# Wildly_4Lipo_Charge.net
KiCad netlist of a schematic drawn in EAGLE
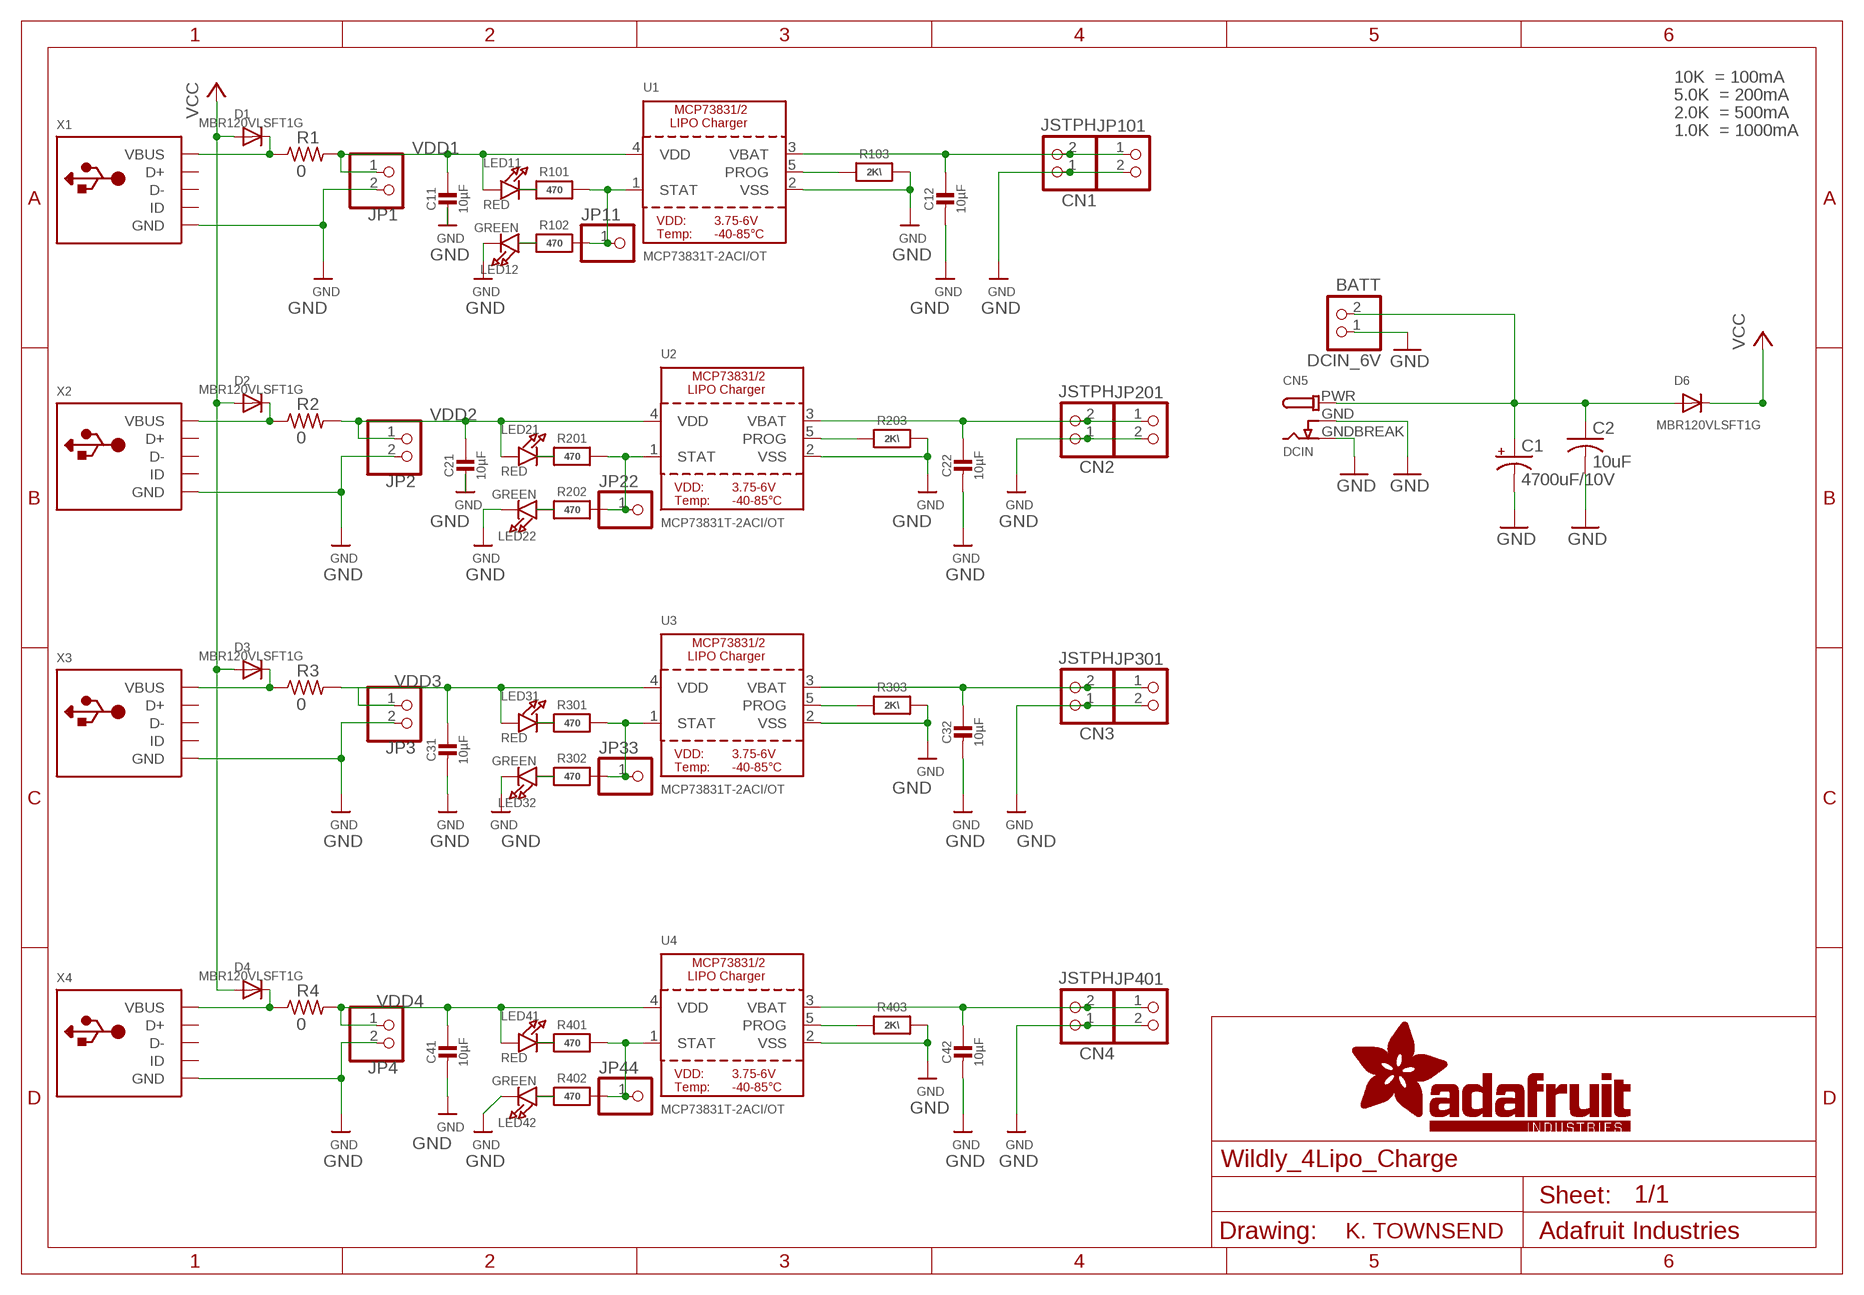
[diagram p0: schematic, sheet 1]

(export (version "E")
  (design (tool "Eeschema 10.0.6"))
  (components
    (comp (ref "C1")
      (value "4700uF/10V")
      (footprint "eagle-import:E5-13")
      (libsource (lib "eagle-import") (part "CPOL-USE5-13"))
    )
    (comp (ref "C2")
      (value "10uF")
      (footprint "eagle-import:C0805K")
      (libsource (lib "eagle-import") (part "C-USC0805K"))
    )
    (comp (ref "C11")
      (value "10µF")
      (footprint "eagle-import:0805-NO")
      (libsource (lib "eagle-import") (part "CAP_CERAMIC0805-NOOUTLINE"))
    )
    (comp (ref "C12")
      (value "10µF")
      (footprint "eagle-import:0805-NO")
      (libsource (lib "eagle-import") (part "CAP_CERAMIC0805-NOOUTLINE"))
    )
    (comp (ref "C21")
      (value "10µF")
      (footprint "eagle-import:0805-NO")
      (libsource (lib "eagle-import") (part "CAP_CERAMIC0805-NOOUTLINE"))
    )
    (comp (ref "C22")
      (value "10µF")
      (footprint "eagle-import:0805-NO")
      (libsource (lib "eagle-import") (part "CAP_CERAMIC0805-NOOUTLINE"))
    )
    (comp (ref "C31")
      (value "10µF")
      (footprint "eagle-import:0805-NO")
      (libsource (lib "eagle-import") (part "CAP_CERAMIC0805-NOOUTLINE"))
    )
    (comp (ref "C32")
      (value "10µF")
      (footprint "eagle-import:0805-NO")
      (libsource (lib "eagle-import") (part "CAP_CERAMIC0805-NOOUTLINE"))
    )
    (comp (ref "C41")
      (value "10µF")
      (footprint "eagle-import:0805-NO")
      (libsource (lib "eagle-import") (part "CAP_CERAMIC0805-NOOUTLINE"))
    )
    (comp (ref "C42")
      (value "10µF")
      (footprint "eagle-import:0805-NO")
      (libsource (lib "eagle-import") (part "CAP_CERAMIC0805-NOOUTLINE"))
    )
    (comp (ref "CN1")
      (value "JSTPH")
      (footprint "eagle-import:JSTPH2")
      (libsource (lib "eagle-import") (part "JST_2PIN"))
    )
    (comp (ref "CN2")
      (value "JSTPH")
      (footprint "eagle-import:JSTPH2")
      (libsource (lib "eagle-import") (part "JST_2PIN"))
    )
    (comp (ref "CN3")
      (value "JSTPH")
      (footprint "eagle-import:JSTPH2")
      (libsource (lib "eagle-import") (part "JST_2PIN"))
    )
    (comp (ref "CN4")
      (value "JSTPH")
      (footprint "eagle-import:JSTPH2")
      (libsource (lib "eagle-import") (part "JST_2PIN"))
    )
    (comp (ref "CN5")
      (value "DCIN")
      (footprint "eagle-import:DCJACK_2MM_SMT")
      (libsource (lib "eagle-import") (part "DCBARRELSMT"))
    )
    (comp (ref "D1")
      (value "MBR120VLSFT1G")
      (footprint "eagle-import:SOD-123")
      (libsource (lib "eagle-import") (part "DIODESOD-123"))
    )
    (comp (ref "D2")
      (value "MBR120VLSFT1G")
      (footprint "eagle-import:SOD-123")
      (libsource (lib "eagle-import") (part "DIODESOD-123"))
    )
    (comp (ref "D3")
      (value "MBR120VLSFT1G")
      (footprint "eagle-import:SOD-123")
      (libsource (lib "eagle-import") (part "DIODESOD-123"))
    )
    (comp (ref "D4")
      (value "MBR120VLSFT1G")
      (footprint "eagle-import:SOD-123")
      (libsource (lib "eagle-import") (part "DIODESOD-123"))
    )
    (comp (ref "D6")
      (value "MBR120VLSFT1G")
      (footprint "eagle-import:SOD-123")
      (libsource (lib "eagle-import") (part "DIODESOD-123"))
    )
    (comp (ref "DCIN_6V")
      (value "BATT")
      (footprint "eagle-import:1X02_ROUND")
      (libsource (lib "eagle-import") (part "HEADER-1X2ROUND"))
    )
    (comp (ref "JP1")
      (value "HEADER-1X2ROUND")
      (footprint "eagle-import:1X02_ROUND")
      (libsource (lib "eagle-import") (part "HEADER-1X2ROUND"))
    )
    (comp (ref "JP2")
      (value "HEADER-1X2ROUND")
      (footprint "eagle-import:1X02_ROUND")
      (libsource (lib "eagle-import") (part "HEADER-1X2ROUND"))
    )
    (comp (ref "JP3")
      (value "HEADER-1X2ROUND")
      (footprint "eagle-import:1X02_ROUND")
      (libsource (lib "eagle-import") (part "HEADER-1X2ROUND"))
    )
    (comp (ref "JP4")
      (value "HEADER-1X2ROUND")
      (footprint "eagle-import:1X02_ROUND")
      (libsource (lib "eagle-import") (part "HEADER-1X2ROUND"))
    )
    (comp (ref "JP11")
      (value "PINHD-1X1CB")
      (footprint "eagle-import:1X01-CLEANBIG")
      (libsource (lib "eagle-import") (part "PINHD-1X1CB"))
    )
    (comp (ref "JP22")
      (value "PINHD-1X1CB")
      (footprint "eagle-import:1X01-CLEANBIG")
      (libsource (lib "eagle-import") (part "PINHD-1X1CB"))
    )
    (comp (ref "JP33")
      (value "PINHD-1X1CB")
      (footprint "eagle-import:1X01-CLEANBIG")
      (libsource (lib "eagle-import") (part "PINHD-1X1CB"))
    )
    (comp (ref "JP44")
      (value "PINHD-1X1CB")
      (footprint "eagle-import:1X01-CLEANBIG")
      (libsource (lib "eagle-import") (part "PINHD-1X1CB"))
    )
    (comp (ref "JP101")
      (value "HEADER-1X2ROUND")
      (footprint "eagle-import:1X02_ROUND")
      (libsource (lib "eagle-import") (part "HEADER-1X2ROUND"))
    )
    (comp (ref "JP201")
      (value "HEADER-1X2ROUND")
      (footprint "eagle-import:1X02_ROUND")
      (libsource (lib "eagle-import") (part "HEADER-1X2ROUND"))
    )
    (comp (ref "JP301")
      (value "HEADER-1X2ROUND")
      (footprint "eagle-import:1X02_ROUND")
      (libsource (lib "eagle-import") (part "HEADER-1X2ROUND"))
    )
    (comp (ref "JP401")
      (value "HEADER-1X2ROUND")
      (footprint "eagle-import:1X02_ROUND")
      (libsource (lib "eagle-import") (part "HEADER-1X2ROUND"))
    )
    (comp (ref "LED11")
      (value "RED")
      (footprint "eagle-import:CHIPLED_0805_NOOUTLINE")
      (libsource (lib "eagle-import") (part "LED0805_NOOUTLINE"))
    )
    (comp (ref "LED12")
      (value "GREEN")
      (footprint "eagle-import:CHIPLED_0805_NOOUTLINE")
      (libsource (lib "eagle-import") (part "LED0805_NOOUTLINE"))
    )
    (comp (ref "LED21")
      (value "RED")
      (footprint "eagle-import:CHIPLED_0805_NOOUTLINE")
      (libsource (lib "eagle-import") (part "LED0805_NOOUTLINE"))
    )
    (comp (ref "LED22")
      (value "GREEN")
      (footprint "eagle-import:CHIPLED_0805_NOOUTLINE")
      (libsource (lib "eagle-import") (part "LED0805_NOOUTLINE"))
    )
    (comp (ref "LED31")
      (value "RED")
      (footprint "eagle-import:CHIPLED_0805_NOOUTLINE")
      (libsource (lib "eagle-import") (part "LED0805_NOOUTLINE"))
    )
    (comp (ref "LED32")
      (value "GREEN")
      (footprint "eagle-import:CHIPLED_0805_NOOUTLINE")
      (libsource (lib "eagle-import") (part "LED0805_NOOUTLINE"))
    )
    (comp (ref "LED41")
      (value "RED")
      (footprint "eagle-import:CHIPLED_0805_NOOUTLINE")
      (libsource (lib "eagle-import") (part "LED0805_NOOUTLINE"))
    )
    (comp (ref "LED42")
      (value "GREEN")
      (footprint "eagle-import:CHIPLED_0805_NOOUTLINE")
      (libsource (lib "eagle-import") (part "LED0805_NOOUTLINE"))
    )
    (comp (ref "R1")
      (value "0")
      (footprint "eagle-import:R0805")
      (libsource (lib "eagle-import") (part "R-US_R0805"))
    )
    (comp (ref "R2")
      (value "0")
      (footprint "eagle-import:R0805")
      (libsource (lib "eagle-import") (part "R-US_R0805"))
    )
    (comp (ref "R3")
      (value "0")
      (footprint "eagle-import:R0805")
      (libsource (lib "eagle-import") (part "R-US_R0805"))
    )
    (comp (ref "R4")
      (value "0")
      (footprint "eagle-import:R0805")
      (libsource (lib "eagle-import") (part "R-US_R0805"))
    )
    (comp (ref "R101")
      (value "470")
      (footprint "eagle-import:0805-NO")
      (libsource (lib "eagle-import") (part "RESISTOR0805_NOOUTLINE"))
    )
    (comp (ref "R102")
      (value "470")
      (footprint "eagle-import:0805-NO")
      (libsource (lib "eagle-import") (part "RESISTOR0805_NOOUTLINE"))
    )
    (comp (ref "R103")
      (value "2K\\")
      (footprint "eagle-import:0805-NO")
      (libsource (lib "eagle-import") (part "RESISTOR0805_NOOUTLINE"))
    )
    (comp (ref "R201")
      (value "470")
      (footprint "eagle-import:0805-NO")
      (libsource (lib "eagle-import") (part "RESISTOR0805_NOOUTLINE"))
    )
    (comp (ref "R202")
      (value "470")
      (footprint "eagle-import:0805-NO")
      (libsource (lib "eagle-import") (part "RESISTOR0805_NOOUTLINE"))
    )
    (comp (ref "R203")
      (value "2K\\")
      (footprint "eagle-import:0805-NO")
      (libsource (lib "eagle-import") (part "RESISTOR0805_NOOUTLINE"))
    )
    (comp (ref "R301")
      (value "470")
      (footprint "eagle-import:0805-NO")
      (libsource (lib "eagle-import") (part "RESISTOR0805_NOOUTLINE"))
    )
    (comp (ref "R302")
      (value "470")
      (footprint "eagle-import:0805-NO")
      (libsource (lib "eagle-import") (part "RESISTOR0805_NOOUTLINE"))
    )
    (comp (ref "R303")
      (value "2K\\")
      (footprint "eagle-import:0805-NO")
      (libsource (lib "eagle-import") (part "RESISTOR0805_NOOUTLINE"))
    )
    (comp (ref "R401")
      (value "470")
      (footprint "eagle-import:0805-NO")
      (libsource (lib "eagle-import") (part "RESISTOR0805_NOOUTLINE"))
    )
    (comp (ref "R402")
      (value "470")
      (footprint "eagle-import:0805-NO")
      (libsource (lib "eagle-import") (part "RESISTOR0805_NOOUTLINE"))
    )
    (comp (ref "R403")
      (value "2K\\")
      (footprint "eagle-import:0805-NO")
      (libsource (lib "eagle-import") (part "RESISTOR0805_NOOUTLINE"))
    )
    (comp (ref "U1")
      (value "MCP73831T-2ACI/OT")
      (footprint "eagle-import:SOT23-5")
      (libsource (lib "eagle-import") (part "MCP73831/2"))
    )
    (comp (ref "U2")
      (value "MCP73831T-2ACI/OT")
      (footprint "eagle-import:SOT23-5")
      (libsource (lib "eagle-import") (part "MCP73831/2"))
    )
    (comp (ref "U3")
      (value "MCP73831T-2ACI/OT")
      (footprint "eagle-import:SOT23-5")
      (libsource (lib "eagle-import") (part "MCP73831/2"))
    )
    (comp (ref "U4")
      (value "MCP73831T-2ACI/OT")
      (footprint "eagle-import:SOT23-5")
      (libsource (lib "eagle-import") (part "MCP73831/2"))
    )
    (comp (ref "X1")
      (value "USB_MEDIUM")
      (footprint "eagle-import:USB-MINI_MEDIUM")
      (libsource (lib "eagle-import") (part "USB_MEDIUM"))
    )
    (comp (ref "X2")
      (value "USB_MEDIUM")
      (footprint "eagle-import:USB-MINI_MEDIUM")
      (libsource (lib "eagle-import") (part "USB_MEDIUM"))
    )
    (comp (ref "X3")
      (value "USB_MEDIUM")
      (footprint "eagle-import:USB-MINI_MEDIUM")
      (libsource (lib "eagle-import") (part "USB_MEDIUM"))
    )
    (comp (ref "X4")
      (value "USB_MEDIUM")
      (footprint "eagle-import:USB-MINI_MEDIUM")
      (libsource (lib "eagle-import") (part "USB_MEDIUM"))
    )
  )
  (nets
    (net (code "1") (name "/VDD1") (class "Default")
      (node (ref "C11") (pin "1") (pinfunction "1_1") (pintype "passive"))
      (node (ref "JP1") (pin "1") (pinfunction "1_1") (pintype "passive"))
      (node (ref "LED11") (pin "A") (pinfunction "A_A") (pintype "passive"))
      (node (ref "R1") (pin "2") (pinfunction "2_2") (pintype "passive"))
      (node (ref "U1") (pin "4") (pinfunction "VDD_4") (pintype "power_in"))
    )
    (net (code "2") (name "/VDD2") (class "Default")
      (node (ref "C21") (pin "1") (pinfunction "1_1") (pintype "passive"))
      (node (ref "JP2") (pin "1") (pinfunction "1_1") (pintype "passive"))
      (node (ref "LED21") (pin "A") (pinfunction "A_A") (pintype "passive"))
      (node (ref "R2") (pin "2") (pinfunction "2_2") (pintype "passive"))
      (node (ref "U2") (pin "4") (pinfunction "VDD_4") (pintype "power_in"))
    )
    (net (code "3") (name "/VDD3") (class "Default")
      (node (ref "C31") (pin "1") (pinfunction "1_1") (pintype "passive"))
      (node (ref "JP3") (pin "1") (pinfunction "1_1") (pintype "passive"))
      (node (ref "LED31") (pin "A") (pinfunction "A_A") (pintype "passive"))
      (node (ref "R3") (pin "2") (pinfunction "2_2") (pintype "passive"))
      (node (ref "U3") (pin "4") (pinfunction "VDD_4") (pintype "power_in"))
    )
    (net (code "4") (name "/VDD4") (class "Default")
      (node (ref "C41") (pin "1") (pinfunction "1_1") (pintype "passive"))
      (node (ref "JP4") (pin "1") (pinfunction "1_1") (pintype "passive"))
      (node (ref "LED41") (pin "A") (pinfunction "A_A") (pintype "passive"))
      (node (ref "R4") (pin "2") (pinfunction "2_2") (pintype "passive"))
      (node (ref "U4") (pin "4") (pinfunction "VDD_4") (pintype "power_in"))
    )
    (net (code "5") (name "GND") (class "Default")
      (node (ref "C1") (pin "-") (pinfunction "-_-") (pintype "passive"))
      (node (ref "C11") (pin "2") (pinfunction "2_2") (pintype "passive"))
      (node (ref "C12") (pin "2") (pinfunction "2_2") (pintype "passive"))
      (node (ref "C2") (pin "2") (pinfunction "2_2") (pintype "passive"))
      (node (ref "C21") (pin "2") (pinfunction "2_2") (pintype "passive"))
      (node (ref "C22") (pin "2") (pinfunction "2_2") (pintype "passive"))
      (node (ref "C31") (pin "2") (pinfunction "2_2") (pintype "passive"))
      (node (ref "C32") (pin "2") (pinfunction "2_2") (pintype "passive"))
      (node (ref "C41") (pin "2") (pinfunction "2_2") (pintype "passive"))
      (node (ref "C42") (pin "2") (pinfunction "2_2") (pintype "passive"))
      (node (ref "CN1") (pin "1") (pinfunction "1_1") (pintype "passive"))
      (node (ref "CN2") (pin "1") (pinfunction "1_1") (pintype "passive"))
      (node (ref "CN3") (pin "1") (pinfunction "1_1") (pintype "passive"))
      (node (ref "CN4") (pin "1") (pinfunction "1_1") (pintype "passive"))
      (node (ref "CN5") (pin "GND") (pinfunction "GNDBREAK_GND") (pintype "power_in"))
      (node (ref "CN5") (pin "GNDBREAK") (pinfunction "GND_GNDBREAK") (pintype "power_in"))
      (node (ref "DCIN_6V") (pin "1") (pinfunction "1_1") (pintype "passive"))
      (node (ref "JP1") (pin "2") (pinfunction "2_2") (pintype "passive"))
      (node (ref "JP101") (pin "2") (pinfunction "2_2") (pintype "passive"))
      (node (ref "JP2") (pin "2") (pinfunction "2_2") (pintype "passive"))
      (node (ref "JP201") (pin "2") (pinfunction "2_2") (pintype "passive"))
      (node (ref "JP3") (pin "2") (pinfunction "2_2") (pintype "passive"))
      (node (ref "JP301") (pin "2") (pinfunction "2_2") (pintype "passive"))
      (node (ref "JP4") (pin "2") (pinfunction "2_2") (pintype "passive"))
      (node (ref "JP401") (pin "2") (pinfunction "2_2") (pintype "passive"))
      (node (ref "LED12") (pin "C") (pinfunction "C_C") (pintype "passive"))
      (node (ref "LED22") (pin "C") (pinfunction "C_C") (pintype "passive"))
      (node (ref "LED32") (pin "C") (pinfunction "C_C") (pintype "passive"))
      (node (ref "LED42") (pin "C") (pinfunction "C_C") (pintype "passive"))
      (node (ref "R103") (pin "2") (pinfunction "2_2") (pintype "passive"))
      (node (ref "R203") (pin "2") (pinfunction "2_2") (pintype "passive"))
      (node (ref "R303") (pin "2") (pinfunction "2_2") (pintype "passive"))
      (node (ref "R403") (pin "2") (pinfunction "2_2") (pintype "passive"))
      (node (ref "U1") (pin "2") (pinfunction "VSS_2") (pintype "power_in"))
      (node (ref "U2") (pin "2") (pinfunction "VSS_2") (pintype "power_in"))
      (node (ref "U3") (pin "2") (pinfunction "VSS_2") (pintype "power_in"))
      (node (ref "U4") (pin "2") (pinfunction "VSS_2") (pintype "power_in"))
      (node (ref "X1") (pin "GND") (pinfunction "GND_GND") (pintype "power_in"))
      (node (ref "X1") (pin "GND1") (pinfunction "GND_GND1") (pintype "power_in"))
      (node (ref "X1") (pin "GND2") (pinfunction "GND_GND2") (pintype "power_in"))
      (node (ref "X1") (pin "GND3") (pinfunction "GND_GND3") (pintype "power_in"))
      (node (ref "X1") (pin "GND4") (pinfunction "GND_GND4") (pintype "power_in"))
      (node (ref "X2") (pin "GND") (pinfunction "GND_GND") (pintype "power_in"))
      (node (ref "X2") (pin "GND1") (pinfunction "GND_GND1") (pintype "power_in"))
      (node (ref "X2") (pin "GND2") (pinfunction "GND_GND2") (pintype "power_in"))
      (node (ref "X2") (pin "GND3") (pinfunction "GND_GND3") (pintype "power_in"))
      (node (ref "X2") (pin "GND4") (pinfunction "GND_GND4") (pintype "power_in"))
      (node (ref "X3") (pin "GND") (pinfunction "GND_GND") (pintype "power_in"))
      (node (ref "X3") (pin "GND1") (pinfunction "GND_GND1") (pintype "power_in"))
      (node (ref "X3") (pin "GND2") (pinfunction "GND_GND2") (pintype "power_in"))
      (node (ref "X3") (pin "GND3") (pinfunction "GND_GND3") (pintype "power_in"))
      (node (ref "X3") (pin "GND4") (pinfunction "GND_GND4") (pintype "power_in"))
      (node (ref "X4") (pin "GND") (pinfunction "GND_GND") (pintype "power_in"))
      (node (ref "X4") (pin "GND1") (pinfunction "GND_GND1") (pintype "power_in"))
      (node (ref "X4") (pin "GND2") (pinfunction "GND_GND2") (pintype "power_in"))
      (node (ref "X4") (pin "GND3") (pinfunction "GND_GND3") (pintype "power_in"))
      (node (ref "X4") (pin "GND4") (pinfunction "GND_GND4") (pintype "power_in"))
    )
    (net (code "6") (name "Net-(C1-Pad+)") (class "Default")
      (node (ref "C1") (pin "+") (pinfunction "+_+") (pintype "passive"))
      (node (ref "C2") (pin "1") (pinfunction "1_1") (pintype "passive"))
      (node (ref "CN5") (pin "PWR") (pinfunction "PWR_PWR") (pintype "power_in"))
      (node (ref "D6") (pin "A") (pinfunction "A_A") (pintype "passive"))
      (node (ref "DCIN_6V") (pin "2") (pinfunction "2_2") (pintype "passive"))
    )
    (net (code "7") (name "Net-(D1-PadC)") (class "Default")
      (node (ref "D1") (pin "C") (pinfunction "C_C") (pintype "passive"))
      (node (ref "R1") (pin "1") (pinfunction "1_1") (pintype "passive"))
      (node (ref "X1") (pin "VBUS") (pinfunction "VBUS_VBUS") (pintype "power_in"))
    )
    (net (code "8") (name "Net-(D2-PadC)") (class "Default")
      (node (ref "D2") (pin "C") (pinfunction "C_C") (pintype "passive"))
      (node (ref "R2") (pin "1") (pinfunction "1_1") (pintype "passive"))
      (node (ref "X2") (pin "VBUS") (pinfunction "VBUS_VBUS") (pintype "power_in"))
    )
    (net (code "9") (name "Net-(D3-PadC)") (class "Default")
      (node (ref "D3") (pin "C") (pinfunction "C_C") (pintype "passive"))
      (node (ref "R3") (pin "1") (pinfunction "1_1") (pintype "passive"))
      (node (ref "X3") (pin "VBUS") (pinfunction "VBUS_VBUS") (pintype "power_in"))
    )
    (net (code "10") (name "Net-(D4-PadC)") (class "Default")
      (node (ref "D4") (pin "C") (pinfunction "C_C") (pintype "passive"))
      (node (ref "R4") (pin "1") (pinfunction "1_1") (pintype "passive"))
      (node (ref "X4") (pin "VBUS") (pinfunction "VBUS_VBUS") (pintype "power_in"))
    )
    (net (code "11") (name "Net-(LED11-PadC)") (class "Default")
      (node (ref "LED11") (pin "C") (pinfunction "C_C") (pintype "passive"))
      (node (ref "R101") (pin "1") (pinfunction "1_1") (pintype "passive"))
    )
    (net (code "12") (name "Net-(LED12-PadA)") (class "Default")
      (node (ref "LED12") (pin "A") (pinfunction "A_A") (pintype "passive"))
      (node (ref "R102") (pin "1") (pinfunction "1_1") (pintype "passive"))
    )
    (net (code "13") (name "Net-(LED21-PadC)") (class "Default")
      (node (ref "LED21") (pin "C") (pinfunction "C_C") (pintype "passive"))
      (node (ref "R201") (pin "1") (pinfunction "1_1") (pintype "passive"))
    )
    (net (code "14") (name "Net-(LED22-PadA)") (class "Default")
      (node (ref "LED22") (pin "A") (pinfunction "A_A") (pintype "passive"))
      (node (ref "R202") (pin "1") (pinfunction "1_1") (pintype "passive"))
    )
    (net (code "15") (name "Net-(LED31-PadC)") (class "Default")
      (node (ref "LED31") (pin "C") (pinfunction "C_C") (pintype "passive"))
      (node (ref "R301") (pin "1") (pinfunction "1_1") (pintype "passive"))
    )
    (net (code "16") (name "Net-(LED32-PadA)") (class "Default")
      (node (ref "LED32") (pin "A") (pinfunction "A_A") (pintype "passive"))
      (node (ref "R302") (pin "1") (pinfunction "1_1") (pintype "passive"))
    )
    (net (code "17") (name "Net-(LED41-PadC)") (class "Default")
      (node (ref "LED41") (pin "C") (pinfunction "C_C") (pintype "passive"))
      (node (ref "R401") (pin "1") (pinfunction "1_1") (pintype "passive"))
    )
    (net (code "18") (name "Net-(LED42-PadA)") (class "Default")
      (node (ref "LED42") (pin "A") (pinfunction "A_A") (pintype "passive"))
      (node (ref "R402") (pin "1") (pinfunction "1_1") (pintype "passive"))
    )
    (net (code "19") (name "Net-(U1-PROG)") (class "Default")
      (node (ref "R103") (pin "1") (pinfunction "1_1") (pintype "passive"))
      (node (ref "U1") (pin "5") (pinfunction "PROG_5") (pintype "input"))
    )
    (net (code "20") (name "Net-(U1-STAT)") (class "Default")
      (node (ref "JP11") (pin "1") (pinfunction "1_1") (pintype "passive"))
      (node (ref "R101") (pin "2") (pinfunction "2_2") (pintype "passive"))
      (node (ref "R102") (pin "2") (pinfunction "2_2") (pintype "passive"))
      (node (ref "U1") (pin "1") (pinfunction "STAT_1") (pintype "output"))
    )
    (net (code "21") (name "Net-(U1-VBAT)") (class "Default")
      (node (ref "C12") (pin "1") (pinfunction "1_1") (pintype "passive"))
      (node (ref "CN1") (pin "2") (pinfunction "2_2") (pintype "passive"))
      (node (ref "JP101") (pin "1") (pinfunction "1_1") (pintype "passive"))
      (node (ref "U1") (pin "3") (pinfunction "VBAT_3") (pintype "power_in"))
    )
    (net (code "22") (name "Net-(U2-PROG)") (class "Default")
      (node (ref "R203") (pin "1") (pinfunction "1_1") (pintype "passive"))
      (node (ref "U2") (pin "5") (pinfunction "PROG_5") (pintype "input"))
    )
    (net (code "23") (name "Net-(U2-STAT)") (class "Default")
      (node (ref "JP22") (pin "1") (pinfunction "1_1") (pintype "passive"))
      (node (ref "R201") (pin "2") (pinfunction "2_2") (pintype "passive"))
      (node (ref "R202") (pin "2") (pinfunction "2_2") (pintype "passive"))
      (node (ref "U2") (pin "1") (pinfunction "STAT_1") (pintype "output"))
    )
    (net (code "24") (name "Net-(U2-VBAT)") (class "Default")
      (node (ref "C22") (pin "1") (pinfunction "1_1") (pintype "passive"))
      (node (ref "CN2") (pin "2") (pinfunction "2_2") (pintype "passive"))
      (node (ref "JP201") (pin "1") (pinfunction "1_1") (pintype "passive"))
      (node (ref "U2") (pin "3") (pinfunction "VBAT_3") (pintype "power_in"))
    )
    (net (code "25") (name "Net-(U3-PROG)") (class "Default")
      (node (ref "R303") (pin "1") (pinfunction "1_1") (pintype "passive"))
      (node (ref "U3") (pin "5") (pinfunction "PROG_5") (pintype "input"))
    )
    (net (code "26") (name "Net-(U3-STAT)") (class "Default")
      (node (ref "JP33") (pin "1") (pinfunction "1_1") (pintype "passive"))
      (node (ref "R301") (pin "2") (pinfunction "2_2") (pintype "passive"))
      (node (ref "R302") (pin "2") (pinfunction "2_2") (pintype "passive"))
      (node (ref "U3") (pin "1") (pinfunction "STAT_1") (pintype "output"))
    )
    (net (code "27") (name "Net-(U3-VBAT)") (class "Default")
      (node (ref "C32") (pin "1") (pinfunction "1_1") (pintype "passive"))
      (node (ref "CN3") (pin "2") (pinfunction "2_2") (pintype "passive"))
      (node (ref "JP301") (pin "1") (pinfunction "1_1") (pintype "passive"))
      (node (ref "U3") (pin "3") (pinfunction "VBAT_3") (pintype "power_in"))
    )
    (net (code "28") (name "Net-(U4-PROG)") (class "Default")
      (node (ref "R403") (pin "1") (pinfunction "1_1") (pintype "passive"))
      (node (ref "U4") (pin "5") (pinfunction "PROG_5") (pintype "input"))
    )
    (net (code "29") (name "Net-(U4-STAT)") (class "Default")
      (node (ref "JP44") (pin "1") (pinfunction "1_1") (pintype "passive"))
      (node (ref "R401") (pin "2") (pinfunction "2_2") (pintype "passive"))
      (node (ref "R402") (pin "2") (pinfunction "2_2") (pintype "passive"))
      (node (ref "U4") (pin "1") (pinfunction "STAT_1") (pintype "output"))
    )
    (net (code "30") (name "Net-(U4-VBAT)") (class "Default")
      (node (ref "C42") (pin "1") (pinfunction "1_1") (pintype "passive"))
      (node (ref "CN4") (pin "2") (pinfunction "2_2") (pintype "passive"))
      (node (ref "JP401") (pin "1") (pinfunction "1_1") (pintype "passive"))
      (node (ref "U4") (pin "3") (pinfunction "VBAT_3") (pintype "power_in"))
    )
    (net (code "31") (name "VCC") (class "Default")
      (node (ref "D1") (pin "A") (pinfunction "A_A") (pintype "passive"))
      (node (ref "D2") (pin "A") (pinfunction "A_A") (pintype "passive"))
      (node (ref "D3") (pin "A") (pinfunction "A_A") (pintype "passive"))
      (node (ref "D4") (pin "A") (pinfunction "A_A") (pintype "passive"))
      (node (ref "D6") (pin "C") (pinfunction "C_C") (pintype "passive"))
    )
    (net (code "32") (name "unconnected-(X1-PadD+)") (class "Default")
      (node (ref "X1") (pin "D+") (pinfunction "D+_D+") (pintype "bidirectional"))
    )
    (net (code "33") (name "unconnected-(X1-PadD-)") (class "Default")
      (node (ref "X1") (pin "D-") (pinfunction "D-_D-") (pintype "bidirectional"))
    )
    (net (code "34") (name "unconnected-(X1-PadID)") (class "Default")
      (node (ref "X1") (pin "ID") (pinfunction "ID_ID") (pintype "bidirectional"))
    )
    (net (code "35") (name "unconnected-(X2-PadD+)") (class "Default")
      (node (ref "X2") (pin "D+") (pinfunction "D+_D+") (pintype "bidirectional"))
    )
    (net (code "36") (name "unconnected-(X2-PadD-)") (class "Default")
      (node (ref "X2") (pin "D-") (pinfunction "D-_D-") (pintype "bidirectional"))
    )
    (net (code "37") (name "unconnected-(X2-PadID)") (class "Default")
      (node (ref "X2") (pin "ID") (pinfunction "ID_ID") (pintype "bidirectional"))
    )
    (net (code "38") (name "unconnected-(X3-PadD+)") (class "Default")
      (node (ref "X3") (pin "D+") (pinfunction "D+_D+") (pintype "bidirectional"))
    )
    (net (code "39") (name "unconnected-(X3-PadD-)") (class "Default")
      (node (ref "X3") (pin "D-") (pinfunction "D-_D-") (pintype "bidirectional"))
    )
    (net (code "40") (name "unconnected-(X3-PadID)") (class "Default")
      (node (ref "X3") (pin "ID") (pinfunction "ID_ID") (pintype "bidirectional"))
    )
    (net (code "41") (name "unconnected-(X4-PadD+)") (class "Default")
      (node (ref "X4") (pin "D+") (pinfunction "D+_D+") (pintype "bidirectional"))
    )
    (net (code "42") (name "unconnected-(X4-PadD-)") (class "Default")
      (node (ref "X4") (pin "D-") (pinfunction "D-_D-") (pintype "bidirectional"))
    )
    (net (code "43") (name "unconnected-(X4-PadID)") (class "Default")
      (node (ref "X4") (pin "ID") (pinfunction "ID_ID") (pintype "bidirectional"))
    )
  )
)
